# HV_Power_Stage.net
KiCad netlist of a schematic drawn in Altium Designer
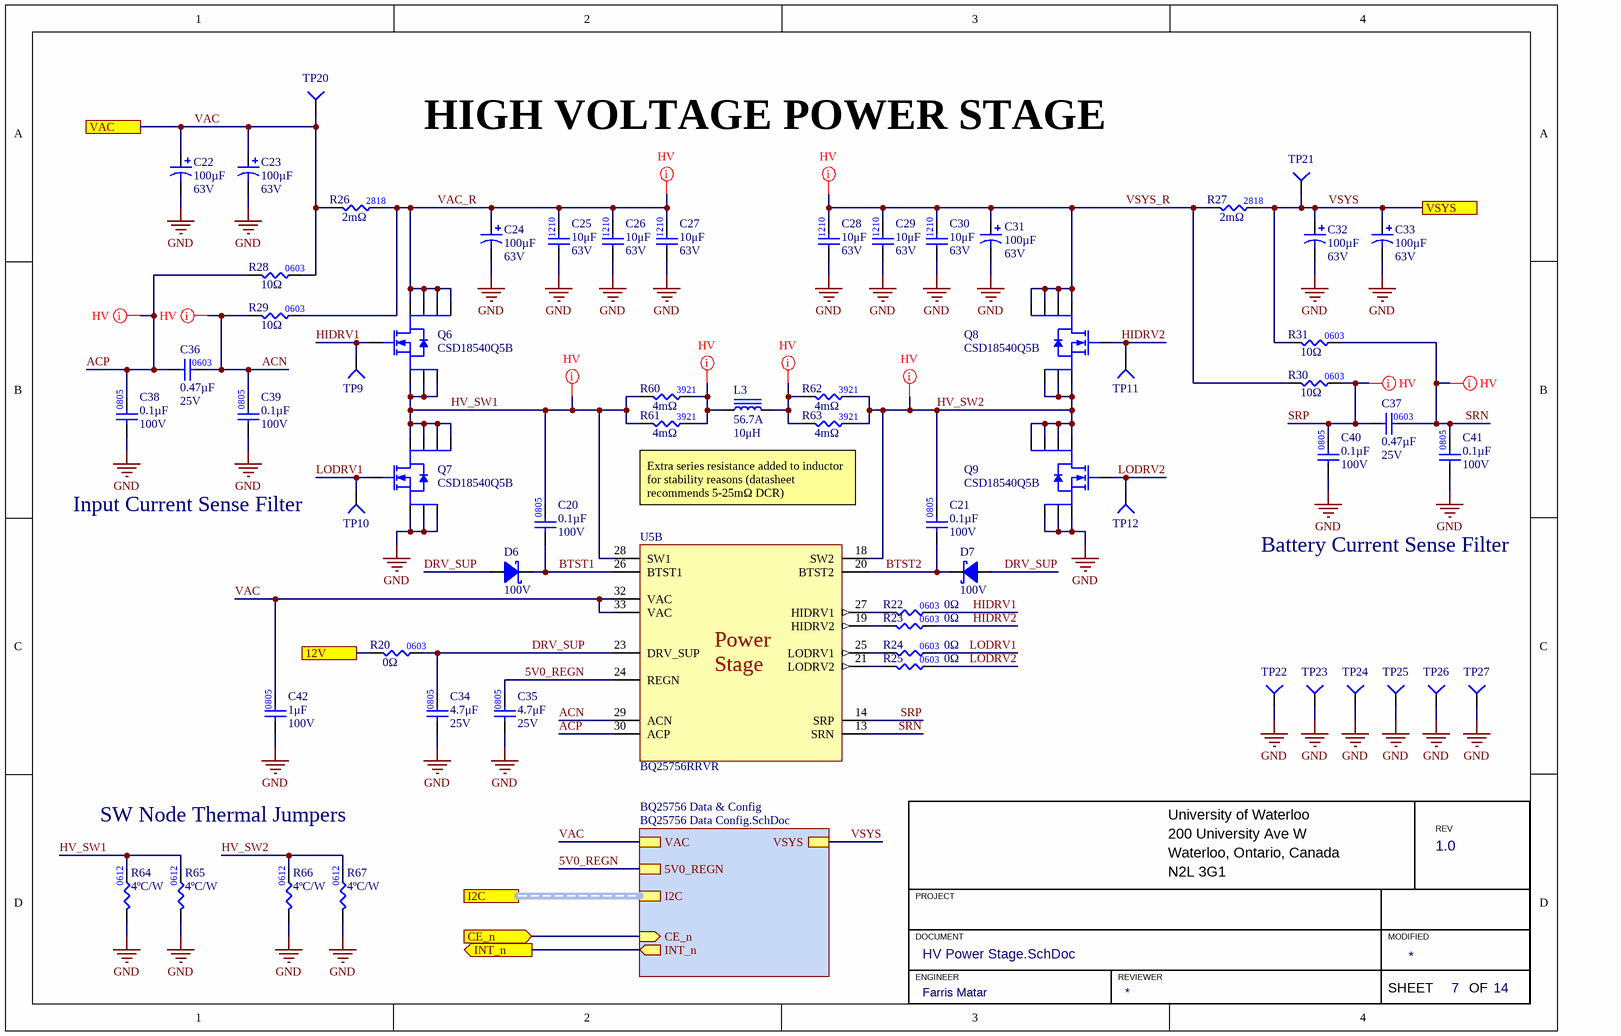
[diagram p0: HV Power Stage.SchDoc]

(export (version "E")
  (design (tool "Eeschema 10.0.6"))
  (components
    (comp (ref "C20")
      (value "0.1µF")
      (footprint "CAP0805")
      (description "CAP CER 0.1UF 100V X7R 0805")
      (fields (field (name "VOLTAGE RATING") "100V") (field (name "Comment") "CAP_0.1uF_100V_0805"))
      (libsource (lib "Personal_Schematic_Library_2022") (part "CAP_0.1uF_100V_0805"))
    )
    (comp (ref "C21")
      (value "0.1µF")
      (footprint "CAP0805")
      (description "CAP CER 0.1UF 100V X7R 0805")
      (fields (field (name "VOLTAGE RATING") "100V") (field (name "Comment") "CAP_0.1uF_100V_0805"))
      (libsource (lib "Personal_Schematic_Library_2022") (part "CAP_0.1uF_100V_0805"))
    )
    (comp (ref "C22")
      (value "100µF")
      (footprint "RADIAL_KEMET_A781")
      (description "CAP ALUMHYB 100UF 20% 63V SMD")
      (fields (field (name "VOLTAGE RATING") "63V") (field (name "Comment") "CAP_100uF_63V_ALUMHYB"))
      (libsource (lib "Personal_Schematic_Library_2022") (part "CAP_100uF_63V_ALUMHYB"))
    )
    (comp (ref "C23")
      (value "100µF")
      (footprint "RADIAL_KEMET_A781")
      (description "CAP ALUMHYB 100UF 20% 63V SMD")
      (fields (field (name "VOLTAGE RATING") "63V") (field (name "Comment") "CAP_100uF_63V_ALUMHYB"))
      (libsource (lib "Personal_Schematic_Library_2022") (part "CAP_100uF_63V_ALUMHYB"))
    )
    (comp (ref "C24")
      (value "100µF")
      (footprint "RADIAL_KEMET_A781")
      (description "CAP ALUMHYB 100UF 20% 63V SMD")
      (fields (field (name "VOLTAGE RATING") "63V") (field (name "Comment") "CAP_100uF_63V_ALUMHYB"))
      (libsource (lib "Personal_Schematic_Library_2022") (part "CAP_100uF_63V_ALUMHYB"))
    )
    (comp (ref "C25")
      (value "10μF")
      (footprint "CAP1210")
      (description "CAP CER 10UF 63V X7R 1210")
      (fields (field (name "VOLTAGE RATING") "63V") (field (name "Comment") "CAP_10uF_63V_1210"))
      (libsource (lib "Personal_Schematic_Library_2022") (part "CAP_10uF_63V_1210"))
    )
    (comp (ref "C26")
      (value "10μF")
      (footprint "CAP1210")
      (description "CAP CER 10UF 63V X7R 1210")
      (fields (field (name "VOLTAGE RATING") "63V") (field (name "Comment") "CAP_10uF_63V_1210"))
      (libsource (lib "Personal_Schematic_Library_2022") (part "CAP_10uF_63V_1210"))
    )
    (comp (ref "C27")
      (value "10μF")
      (footprint "CAP1210")
      (description "CAP CER 10UF 63V X7R 1210")
      (fields (field (name "VOLTAGE RATING") "63V") (field (name "Comment") "CAP_10uF_63V_1210"))
      (libsource (lib "Personal_Schematic_Library_2022") (part "CAP_10uF_63V_1210"))
    )
    (comp (ref "C28")
      (value "10μF")
      (footprint "CAP1210")
      (description "CAP CER 10UF 63V X7R 1210")
      (fields (field (name "VOLTAGE RATING") "63V") (field (name "Comment") "CAP_10uF_63V_1210"))
      (libsource (lib "Personal_Schematic_Library_2022") (part "CAP_10uF_63V_1210"))
    )
    (comp (ref "C29")
      (value "10μF")
      (footprint "CAP1210")
      (description "CAP CER 10UF 63V X7R 1210")
      (fields (field (name "VOLTAGE RATING") "63V") (field (name "Comment") "CAP_10uF_63V_1210"))
      (libsource (lib "Personal_Schematic_Library_2022") (part "CAP_10uF_63V_1210"))
    )
    (comp (ref "C30")
      (value "10μF")
      (footprint "CAP1210")
      (description "CAP CER 10UF 63V X7R 1210")
      (fields (field (name "VOLTAGE RATING") "63V") (field (name "Comment") "CAP_10uF_63V_1210"))
      (libsource (lib "Personal_Schematic_Library_2022") (part "CAP_10uF_63V_1210"))
    )
    (comp (ref "C31")
      (value "100µF")
      (footprint "RADIAL_KEMET_A781")
      (description "CAP ALUMHYB 100UF 20% 63V SMD")
      (fields (field (name "VOLTAGE RATING") "63V") (field (name "Comment") "CAP_100uF_63V_ALUMHYB"))
      (libsource (lib "Personal_Schematic_Library_2022") (part "CAP_100uF_63V_ALUMHYB"))
    )
    (comp (ref "C32")
      (value "100µF")
      (footprint "RADIAL_KEMET_A781")
      (description "CAP ALUMHYB 100UF 20% 63V SMD")
      (fields (field (name "VOLTAGE RATING") "63V") (field (name "Comment") "CAP_100uF_63V_ALUMHYB"))
      (libsource (lib "Personal_Schematic_Library_2022") (part "CAP_100uF_63V_ALUMHYB"))
    )
    (comp (ref "C33")
      (value "100µF")
      (footprint "RADIAL_KEMET_A781")
      (description "CAP ALUMHYB 100UF 20% 63V SMD")
      (fields (field (name "VOLTAGE RATING") "63V") (field (name "Comment") "CAP_100uF_63V_ALUMHYB"))
      (libsource (lib "Personal_Schematic_Library_2022") (part "CAP_100uF_63V_ALUMHYB"))
    )
    (comp (ref "C34")
      (value "4.7μF")
      (footprint "CAP0805")
      (description "CAP CER 4.7UF 25V X7R 0805")
      (fields (field (name "VOLTAGE RATING") "25V") (field (name "Comment") "CAP_4.7uF_25V_0805"))
      (libsource (lib "Personal_Schematic_Library_2022") (part "CAP_4.7uF_25V_0805"))
    )
    (comp (ref "C35")
      (value "4.7μF")
      (footprint "CAP0805")
      (description "CAP CER 4.7UF 25V X7R 0805")
      (fields (field (name "VOLTAGE RATING") "25V") (field (name "Comment") "CAP_4.7uF_25V_0805"))
      (libsource (lib "Personal_Schematic_Library_2022") (part "CAP_4.7uF_25V_0805"))
    )
    (comp (ref "C36")
      (value "0.47µF")
      (footprint "CAP0603")
      (description "CAP CER 0.47UF 25V X7R 0603")
      (fields (field (name "VOLTAGE RATING") "25V") (field (name "Comment") "CAP_0.47uF_25V_0603"))
      (libsource (lib "Personal_Schematic_Library_2022") (part "CAP_0.47uF_25V_0603"))
    )
    (comp (ref "C37")
      (value "0.47µF")
      (footprint "CAP0603")
      (description "CAP CER 0.47UF 25V X7R 0603")
      (fields (field (name "VOLTAGE RATING") "25V") (field (name "Comment") "CAP_0.47uF_25V_0603"))
      (libsource (lib "Personal_Schematic_Library_2022") (part "CAP_0.47uF_25V_0603"))
    )
    (comp (ref "C38")
      (value "0.1µF")
      (footprint "CAP0805")
      (description "CAP CER 0.1UF 100V X7R 0805")
      (fields (field (name "VOLTAGE RATING") "100V") (field (name "Comment") "CAP_0.1uF_100V_0805"))
      (libsource (lib "Personal_Schematic_Library_2022") (part "CAP_0.1uF_100V_0805"))
    )
    (comp (ref "C39")
      (value "0.1µF")
      (footprint "CAP0805")
      (description "CAP CER 0.1UF 100V X7R 0805")
      (fields (field (name "VOLTAGE RATING") "100V") (field (name "Comment") "CAP_0.1uF_100V_0805"))
      (libsource (lib "Personal_Schematic_Library_2022") (part "CAP_0.1uF_100V_0805"))
    )
    (comp (ref "C40")
      (value "0.1µF")
      (footprint "CAP0805")
      (description "CAP CER 0.1UF 100V X7R 0805")
      (fields (field (name "VOLTAGE RATING") "100V") (field (name "Comment") "CAP_0.1uF_100V_0805"))
      (libsource (lib "Personal_Schematic_Library_2022") (part "CAP_0.1uF_100V_0805"))
    )
    (comp (ref "C41")
      (value "0.1µF")
      (footprint "CAP0805")
      (description "CAP CER 0.1UF 100V X7R 0805")
      (fields (field (name "VOLTAGE RATING") "100V") (field (name "Comment") "CAP_0.1uF_100V_0805"))
      (libsource (lib "Personal_Schematic_Library_2022") (part "CAP_0.1uF_100V_0805"))
    )
    (comp (ref "C42")
      (value "1μF")
      (footprint "CAP0805")
      (description "CAP CER 1UF 100V X7R 0805")
      (fields (field (name "VOLTAGE RATING") "100V") (field (name "Comment") "CAP_1uF_100V_0805"))
      (libsource (lib "Personal_Schematic_Library_2022") (part "CAP_1uF_100V_0805"))
    )
    (comp (ref "D6")
      (value "DIO_SCHOTTKY_100V_2A")
      (footprint "SOD-123_FLAT")
      (description "DIODE SCHOTTKY 100V 2A SOD123F")
      (fields (field (name "VR (MAX)") "100V"))
      (libsource (lib "Personal_Schematic_Library_2022") (part "DIO_SCHOTTKY_100V_2A"))
    )
    (comp (ref "D7")
      (value "DIO_SCHOTTKY_100V_2A")
      (footprint "SOD-123_FLAT")
      (description "DIODE SCHOTTKY 100V 2A SOD123F")
      (fields (field (name "VR (MAX)") "100V"))
      (libsource (lib "Personal_Schematic_Library_2022") (part "DIO_SCHOTTKY_100V_2A"))
    )
    (comp (ref "L3")
      (value "IND_10uH_56.7A")
      (footprint "IND_WURTH_HCFT_TH")
      (description "FIXED IND 10UH 56.7A 1.2 MOHM TH")
      (fields (field (name "CURRENT RATING") "56.7A") (field (name "INDUCTANCE") "10μH"))
      (libsource (lib "Personal_Schematic_Library_2022") (part "IND_10uH_56.7A"))
    )
    (comp (ref "Q6")
      (value "NMOS_60V_100A_TI")
      (footprint "DFN5060")
      (description "MOSFET N-CH 60V 100A 8VSON")
      (fields (field (name "MANUFACTURER PART NUMBER 1") "CSD18540Q5B"))
      (libsource (lib "Personal_Schematic_Library_2022") (part "NMOS_60V_100A_TI"))
    )
    (comp (ref "Q7")
      (value "NMOS_60V_100A_TI")
      (footprint "DFN5060")
      (description "MOSFET N-CH 60V 100A 8VSON")
      (fields (field (name "MANUFACTURER PART NUMBER 1") "CSD18540Q5B"))
      (libsource (lib "Personal_Schematic_Library_2022") (part "NMOS_60V_100A_TI"))
    )
    (comp (ref "Q8")
      (value "NMOS_60V_100A_TI")
      (footprint "DFN5060")
      (description "MOSFET N-CH 60V 100A 8VSON")
      (fields (field (name "MANUFACTURER PART NUMBER 1") "CSD18540Q5B"))
      (libsource (lib "Personal_Schematic_Library_2022") (part "NMOS_60V_100A_TI"))
    )
    (comp (ref "Q9")
      (value "NMOS_60V_100A_TI")
      (footprint "DFN5060")
      (description "MOSFET N-CH 60V 100A 8VSON")
      (fields (field (name "MANUFACTURER PART NUMBER 1") "CSD18540Q5B"))
      (libsource (lib "Personal_Schematic_Library_2022") (part "NMOS_60V_100A_TI"))
    )
    (comp (ref "R20")
      (value "0Ω")
      (footprint "RES0603")
      (description "RES 0 OHM JUMPER 1/10W 0603")
      (fields (field (name "Comment") "RES_0Ω_0603"))
      (libsource (lib "Personal_Schematic_Library_2022") (part "RES_0Ω_0603"))
    )
    (comp (ref "R22")
      (value "0Ω")
      (footprint "RES0603")
      (description "RES 0 OHM JUMPER 1/10W 0603")
      (fields (field (name "Comment") "RES_0Ω_0603"))
      (libsource (lib "Personal_Schematic_Library_2022") (part "RES_0Ω_0603"))
    )
    (comp (ref "R23")
      (value "0Ω")
      (footprint "RES0603")
      (description "RES 0 OHM JUMPER 1/10W 0603")
      (fields (field (name "Comment") "RES_0Ω_0603"))
      (libsource (lib "Personal_Schematic_Library_2022") (part "RES_0Ω_0603"))
    )
    (comp (ref "R24")
      (value "0Ω")
      (footprint "RES0603")
      (description "RES 0 OHM JUMPER 1/10W 0603")
      (fields (field (name "Comment") "RES_0Ω_0603"))
      (libsource (lib "Personal_Schematic_Library_2022") (part "RES_0Ω_0603"))
    )
    (comp (ref "R25")
      (value "0Ω")
      (footprint "RES0603")
      (description "RES 0 OHM JUMPER 1/10W 0603")
      (fields (field (name "Comment") "RES_0Ω_0603"))
      (libsource (lib "Personal_Schematic_Library_2022") (part "RES_0Ω_0603"))
    )
    (comp (ref "R26")
      (value "2mΩ")
      (footprint "RES2812_VISHAY")
      (description "RES 0.002 OHM 1% 10W 2818")
      (fields (field (name "Comment") "RES_2mΩ_2818_1%"))
      (libsource (lib "Personal_Schematic_Library_2022") (part "RES_2mΩ_2818_1%"))
    )
    (comp (ref "R27")
      (value "2mΩ")
      (footprint "RES2812_VISHAY")
      (description "RES 0.002 OHM 1% 10W 2818")
      (fields (field (name "Comment") "RES_2mΩ_2818_1%"))
      (libsource (lib "Personal_Schematic_Library_2022") (part "RES_2mΩ_2818_1%"))
    )
    (comp (ref "R28")
      (value "10Ω")
      (footprint "RES0603")
      (description "RES 10 OHM 1% 1/10W 0603")
      (fields (field (name "Comment") "RES_10Ω_0603_1%"))
      (libsource (lib "Personal_Schematic_Library_2022") (part "RES_10Ω_0603_1%"))
    )
    (comp (ref "R29")
      (value "10Ω")
      (footprint "RES0603")
      (description "RES 10 OHM 1% 1/10W 0603")
      (fields (field (name "Comment") "RES_10Ω_0603_1%"))
      (libsource (lib "Personal_Schematic_Library_2022") (part "RES_10Ω_0603_1%"))
    )
    (comp (ref "R30")
      (value "10Ω")
      (footprint "RES0603")
      (description "RES 10 OHM 1% 1/10W 0603")
      (fields (field (name "Comment") "RES_10Ω_0603_1%"))
      (libsource (lib "Personal_Schematic_Library_2022") (part "RES_10Ω_0603_1%"))
    )
    (comp (ref "R31")
      (value "10Ω")
      (footprint "RES0603")
      (description "RES 10 OHM 1% 1/10W 0603")
      (fields (field (name "Comment") "RES_10Ω_0603_1%"))
      (libsource (lib "Personal_Schematic_Library_2022") (part "RES_10Ω_0603_1%"))
    )
    (comp (ref "R60")
      (value "4mΩ")
      (footprint "RES3921")
      (description "RES 0.004 OHM 1% 5W 3921")
      (fields (field (name "Comment") "RES_4mΩ_3921_1%"))
      (libsource (lib "Personal_Schematic_Library_2022") (part "RES_4mΩ_3921_1%"))
    )
    (comp (ref "R61")
      (value "4mΩ")
      (footprint "RES3921")
      (description "RES 0.004 OHM 1% 5W 3921")
      (fields (field (name "Comment") "RES_4mΩ_3921_1%"))
      (libsource (lib "Personal_Schematic_Library_2022") (part "RES_4mΩ_3921_1%"))
    )
    (comp (ref "R62")
      (value "4mΩ")
      (footprint "RES3921")
      (description "RES 0.004 OHM 1% 5W 3921")
      (fields (field (name "Comment") "RES_4mΩ_3921_1%"))
      (libsource (lib "Personal_Schematic_Library_2022") (part "RES_4mΩ_3921_1%"))
    )
    (comp (ref "R63")
      (value "4mΩ")
      (footprint "RES3921")
      (description "RES 0.004 OHM 1% 5W 3921")
      (fields (field (name "Comment") "RES_4mΩ_3921_1%"))
      (libsource (lib "Personal_Schematic_Library_2022") (part "RES_4mΩ_3921_1%"))
    )
    (comp (ref "R64")
      (value "4ºC/W")
      (footprint "RES0612")
      (description "THERMAL JUMPER 0612 30 MIL LEAD-")
      (fields (field (name "Comment") "THERM_JMP_4C_0612"))
      (libsource (lib "Personal_Schematic_Library_2022") (part "THERM_JMP_4C_0612"))
    )
    (comp (ref "R65")
      (value "4ºC/W")
      (footprint "RES0612")
      (description "THERMAL JUMPER 0612 30 MIL LEAD-")
      (fields (field (name "Comment") "THERM_JMP_4C_0612"))
      (libsource (lib "Personal_Schematic_Library_2022") (part "THERM_JMP_4C_0612"))
    )
    (comp (ref "R66")
      (value "4ºC/W")
      (footprint "RES0612")
      (description "THERMAL JUMPER 0612 30 MIL LEAD-")
      (fields (field (name "Comment") "THERM_JMP_4C_0612"))
      (libsource (lib "Personal_Schematic_Library_2022") (part "THERM_JMP_4C_0612"))
    )
    (comp (ref "R67")
      (value "4ºC/W")
      (footprint "RES0612")
      (description "THERMAL JUMPER 0612 30 MIL LEAD-")
      (fields (field (name "Comment") "THERM_JMP_4C_0612"))
      (libsource (lib "Personal_Schematic_Library_2022") (part "THERM_JMP_4C_0612"))
    )
    (comp (ref "TP9")
      (value "TESTPOINT_1MM_CIRCLE")
      (footprint "TESTPOINT_CIRCLE_1MM")
      (description "TESTPOINT 1MM CIRCLE")
      (libsource (lib "Personal_Schematic_Library_2022") (part "TESTPOINT_1MM_CIRCLE"))
    )
    (comp (ref "TP10")
      (value "TESTPOINT_1MM_CIRCLE")
      (footprint "TESTPOINT_CIRCLE_1MM")
      (description "TESTPOINT 1MM CIRCLE")
      (libsource (lib "Personal_Schematic_Library_2022") (part "TESTPOINT_1MM_CIRCLE"))
    )
    (comp (ref "TP11")
      (value "TESTPOINT_1MM_CIRCLE")
      (footprint "TESTPOINT_CIRCLE_1MM")
      (description "TESTPOINT 1MM CIRCLE")
      (libsource (lib "Personal_Schematic_Library_2022") (part "TESTPOINT_1MM_CIRCLE"))
    )
    (comp (ref "TP12")
      (value "TESTPOINT_1MM_CIRCLE")
      (footprint "TESTPOINT_CIRCLE_1MM")
      (description "TESTPOINT 1MM CIRCLE")
      (libsource (lib "Personal_Schematic_Library_2022") (part "TESTPOINT_1MM_CIRCLE"))
    )
    (comp (ref "TP20")
      (value "TESTPOINT_KEYSTONE_LOOP")
      (footprint "KEYSTONE_5019")
      (description "PC TEST POINT MINIATURE")
      (libsource (lib "Personal_Schematic_Library_2022") (part "TESTPOINT_KEYSTONE_LOOP"))
    )
    (comp (ref "TP21")
      (value "TESTPOINT_KEYSTONE_LOOP")
      (footprint "KEYSTONE_5019")
      (description "PC TEST POINT MINIATURE")
      (libsource (lib "Personal_Schematic_Library_2022") (part "TESTPOINT_KEYSTONE_LOOP"))
    )
    (comp (ref "TP22")
      (value "TESTPOINT_KEYSTONE_LOOP")
      (footprint "KEYSTONE_5019")
      (description "PC TEST POINT MINIATURE")
      (libsource (lib "Personal_Schematic_Library_2022") (part "TESTPOINT_KEYSTONE_LOOP"))
    )
    (comp (ref "TP23")
      (value "TESTPOINT_KEYSTONE_LOOP")
      (footprint "KEYSTONE_5019")
      (description "PC TEST POINT MINIATURE")
      (libsource (lib "Personal_Schematic_Library_2022") (part "TESTPOINT_KEYSTONE_LOOP"))
    )
    (comp (ref "TP24")
      (value "TESTPOINT_KEYSTONE_LOOP")
      (footprint "KEYSTONE_5019")
      (description "PC TEST POINT MINIATURE")
      (libsource (lib "Personal_Schematic_Library_2022") (part "TESTPOINT_KEYSTONE_LOOP"))
    )
    (comp (ref "TP25")
      (value "TESTPOINT_KEYSTONE_LOOP")
      (footprint "KEYSTONE_5019")
      (description "PC TEST POINT MINIATURE")
      (libsource (lib "Personal_Schematic_Library_2022") (part "TESTPOINT_KEYSTONE_LOOP"))
    )
    (comp (ref "TP26")
      (value "TESTPOINT_KEYSTONE_LOOP")
      (footprint "KEYSTONE_5019")
      (description "PC TEST POINT MINIATURE")
      (libsource (lib "Personal_Schematic_Library_2022") (part "TESTPOINT_KEYSTONE_LOOP"))
    )
    (comp (ref "TP27")
      (value "TESTPOINT_KEYSTONE_LOOP")
      (footprint "KEYSTONE_5019")
      (description "PC TEST POINT MINIATURE")
      (libsource (lib "Personal_Schematic_Library_2022") (part "TESTPOINT_KEYSTONE_LOOP"))
    )
    (comp (ref "U5")
      (value "BQ25756RRVR")
      (footprint "TI_36-VQFN")
      (description "IC BATT CHARGER BUCK-BOOST CTRLR")
      (libsource (lib "Personal_Schematic_Library_2022") (part "BQ25756RRVR"))
    )
  )
  (nets
    (net (code "2") (name "/5V0_REGN") (class "Default")
      (node (ref "C35") (pin "2") (pinfunction "2_2") (pintype "passive"))
      (node (ref "U5") (pin "24") (pinfunction "REGN_24") (pintype "power_in"))
    )
    (net (code "3") (name "/12V") (class "Default")
      (node (ref "R20") (pin "1") (pinfunction "1_1") (pintype "passive"))
    )
    (net (code "4") (name "/ACN") (class "Default")
      (node (ref "C36") (pin "2") (pinfunction "2_2") (pintype "passive"))
      (node (ref "C39") (pin "2") (pinfunction "2_2") (pintype "passive"))
      (node (ref "R29") (pin "1") (pinfunction "1_1") (pintype "passive"))
      (node (ref "U5") (pin "29") (pinfunction "ACN_29") (pintype "passive"))
    )
    (net (code "5") (name "/ACP") (class "Default")
      (node (ref "C36") (pin "1") (pinfunction "1_1") (pintype "passive"))
      (node (ref "C38") (pin "2") (pinfunction "2_2") (pintype "passive"))
      (node (ref "R28") (pin "1") (pinfunction "1_1") (pintype "passive"))
      (node (ref "U5") (pin "30") (pinfunction "ACP_30") (pintype "passive"))
    )
    (net (code "6") (name "/BTST1") (class "Default")
      (node (ref "C20") (pin "1") (pinfunction "1_1") (pintype "passive"))
      (node (ref "D6") (pin "2") (pinfunction "Cathode_2") (pintype "passive"))
      (node (ref "U5") (pin "26") (pinfunction "BTST1_26") (pintype "power_in"))
    )
    (net (code "7") (name "/BTST2") (class "Default")
      (node (ref "C21") (pin "1") (pinfunction "1_1") (pintype "passive"))
      (node (ref "D7") (pin "2") (pinfunction "Cathode_2") (pintype "passive"))
      (node (ref "U5") (pin "20") (pinfunction "BTST2_20") (pintype "power_in"))
    )
    (net (code "9") (name "/DRV_SUP") (class "Default")
      (node (ref "C34") (pin "2") (pinfunction "2_2") (pintype "passive"))
      (node (ref "D6") (pin "1") (pinfunction "Anode_1") (pintype "passive"))
      (node (ref "D7") (pin "1") (pinfunction "Anode_1") (pintype "passive"))
      (node (ref "R20") (pin "2") (pinfunction "2_2") (pintype "passive"))
      (node (ref "U5") (pin "23") (pinfunction "DRV_SUP_23") (pintype "power_in"))
    )
    (net (code "10") (name "/HIDRV1") (class "Default")
      (node (ref "Q6") (pin "4") (pinfunction "Gate_4") (pintype "passive"))
      (node (ref "R22") (pin "2") (pinfunction "2_2") (pintype "passive"))
      (node (ref "TP9") (pin "1") (pinfunction "=value_1") (pintype "passive"))
    )
    (net (code "11") (name "/HIDRV2") (class "Default")
      (node (ref "Q8") (pin "4") (pinfunction "Gate_4") (pintype "passive"))
      (node (ref "R23") (pin "2") (pinfunction "2_2") (pintype "passive"))
      (node (ref "TP11") (pin "1") (pinfunction "=value_1") (pintype "passive"))
    )
    (net (code "12") (name "/HV_SW1") (class "Default")
      (node (ref "C20") (pin "2") (pinfunction "2_2") (pintype "passive"))
      (node (ref "Q6") (pin "1") (pinfunction "Source_1") (pintype "passive"))
      (node (ref "Q6") (pin "2") (pinfunction "Source_2") (pintype "passive"))
      (node (ref "Q6") (pin "3") (pinfunction "Source_3") (pintype "passive"))
      (node (ref "Q7") (pin "5") (pinfunction "Drain_5") (pintype "passive"))
      (node (ref "Q7") (pin "6") (pinfunction "Drain_6") (pintype "passive"))
      (node (ref "Q7") (pin "7") (pinfunction "Drain_7") (pintype "passive"))
      (node (ref "Q7") (pin "8") (pinfunction "Drain_8") (pintype "passive"))
      (node (ref "R60") (pin "1") (pinfunction "1_1") (pintype "passive"))
      (node (ref "R61") (pin "1") (pinfunction "1_1") (pintype "passive"))
      (node (ref "R64") (pin "2") (pinfunction "2_2") (pintype "passive"))
      (node (ref "R65") (pin "2") (pinfunction "2_2") (pintype "passive"))
      (node (ref "U5") (pin "28") (pinfunction "SW1_28") (pintype "power_in"))
    )
    (net (code "13") (name "/HV_SW2") (class "Default")
      (node (ref "C21") (pin "2") (pinfunction "2_2") (pintype "passive"))
      (node (ref "Q8") (pin "1") (pinfunction "Source_1") (pintype "passive"))
      (node (ref "Q8") (pin "2") (pinfunction "Source_2") (pintype "passive"))
      (node (ref "Q8") (pin "3") (pinfunction "Source_3") (pintype "passive"))
      (node (ref "Q9") (pin "5") (pinfunction "Drain_5") (pintype "passive"))
      (node (ref "Q9") (pin "6") (pinfunction "Drain_6") (pintype "passive"))
      (node (ref "Q9") (pin "7") (pinfunction "Drain_7") (pintype "passive"))
      (node (ref "Q9") (pin "8") (pinfunction "Drain_8") (pintype "passive"))
      (node (ref "R62") (pin "2") (pinfunction "2_2") (pintype "passive"))
      (node (ref "R63") (pin "2") (pinfunction "2_2") (pintype "passive"))
      (node (ref "R66") (pin "2") (pinfunction "2_2") (pintype "passive"))
      (node (ref "R67") (pin "2") (pinfunction "2_2") (pintype "passive"))
      (node (ref "U5") (pin "18") (pinfunction "SW2_18") (pintype "power_in"))
    )
    (net (code "16") (name "/LODRV1") (class "Default")
      (node (ref "Q7") (pin "4") (pinfunction "Gate_4") (pintype "passive"))
      (node (ref "R24") (pin "2") (pinfunction "2_2") (pintype "passive"))
      (node (ref "TP10") (pin "1") (pinfunction "=value_1") (pintype "passive"))
    )
    (net (code "17") (name "/LODRV2") (class "Default")
      (node (ref "Q9") (pin "4") (pinfunction "Gate_4") (pintype "passive"))
      (node (ref "R25") (pin "2") (pinfunction "2_2") (pintype "passive"))
      (node (ref "TP12") (pin "1") (pinfunction "=value_1") (pintype "passive"))
    )
    (net (code "18") (name "/SRN") (class "Default")
      (node (ref "C37") (pin "2") (pinfunction "2_2") (pintype "passive"))
      (node (ref "C41") (pin "2") (pinfunction "2_2") (pintype "passive"))
      (node (ref "R31") (pin "2") (pinfunction "2_2") (pintype "passive"))
      (node (ref "U5") (pin "13") (pinfunction "SRN_13") (pintype "passive"))
    )
    (net (code "19") (name "/SRP") (class "Default")
      (node (ref "C37") (pin "1") (pinfunction "1_1") (pintype "passive"))
      (node (ref "C40") (pin "2") (pinfunction "2_2") (pintype "passive"))
      (node (ref "R30") (pin "2") (pinfunction "2_2") (pintype "passive"))
      (node (ref "U5") (pin "14") (pinfunction "SRP_14") (pintype "passive"))
    )
    (net (code "20") (name "/VAC") (class "Default")
      (node (ref "C22") (pin "1") (pinfunction "1_1") (pintype "passive"))
      (node (ref "C23") (pin "1") (pinfunction "1_1") (pintype "passive"))
      (node (ref "C42") (pin "2") (pinfunction "2_2") (pintype "passive"))
      (node (ref "R26") (pin "1") (pinfunction "1_1") (pintype "passive"))
      (node (ref "R28") (pin "2") (pinfunction "2_2") (pintype "passive"))
      (node (ref "TP20") (pin "1") (pinfunction "=value_1") (pintype "passive"))
      (node (ref "U5") (pin "32") (pinfunction "VAC_32") (pintype "power_in"))
      (node (ref "U5") (pin "33") (pinfunction "VAC_33") (pintype "power_in"))
    )
    (net (code "21") (name "/VAC_R") (class "Default")
      (node (ref "C24") (pin "1") (pinfunction "1_1") (pintype "passive"))
      (node (ref "C25") (pin "2") (pinfunction "2_2") (pintype "passive"))
      (node (ref "C26") (pin "2") (pinfunction "2_2") (pintype "passive"))
      (node (ref "C27") (pin "2") (pinfunction "2_2") (pintype "passive"))
      (node (ref "Q6") (pin "5") (pinfunction "Drain_5") (pintype "passive"))
      (node (ref "Q6") (pin "6") (pinfunction "Drain_6") (pintype "passive"))
      (node (ref "Q6") (pin "7") (pinfunction "Drain_7") (pintype "passive"))
      (node (ref "Q6") (pin "8") (pinfunction "Drain_8") (pintype "passive"))
      (node (ref "R26") (pin "2") (pinfunction "2_2") (pintype "passive"))
      (node (ref "R29") (pin "2") (pinfunction "2_2") (pintype "passive"))
    )
    (net (code "22") (name "/VSYS") (class "Default")
      (node (ref "C32") (pin "1") (pinfunction "1_1") (pintype "passive"))
      (node (ref "C33") (pin "1") (pinfunction "1_1") (pintype "passive"))
      (node (ref "R27") (pin "2") (pinfunction "2_2") (pintype "passive"))
      (node (ref "R31") (pin "1") (pinfunction "1_1") (pintype "passive"))
      (node (ref "TP21") (pin "1") (pinfunction "=value_1") (pintype "passive"))
    )
    (net (code "23") (name "/VSYS_R") (class "Default")
      (node (ref "C28") (pin "2") (pinfunction "2_2") (pintype "passive"))
      (node (ref "C29") (pin "2") (pinfunction "2_2") (pintype "passive"))
      (node (ref "C30") (pin "2") (pinfunction "2_2") (pintype "passive"))
      (node (ref "C31") (pin "1") (pinfunction "1_1") (pintype "passive"))
      (node (ref "Q8") (pin "5") (pinfunction "Drain_5") (pintype "passive"))
      (node (ref "Q8") (pin "6") (pinfunction "Drain_6") (pintype "passive"))
      (node (ref "Q8") (pin "7") (pinfunction "Drain_7") (pintype "passive"))
      (node (ref "Q8") (pin "8") (pinfunction "Drain_8") (pintype "passive"))
      (node (ref "R27") (pin "1") (pinfunction "1_1") (pintype "passive"))
      (node (ref "R30") (pin "1") (pinfunction "1_1") (pintype "passive"))
    )
    (net (code "24") (name "GND") (class "Default")
      (node (ref "C22") (pin "2") (pinfunction "2_2") (pintype "passive"))
      (node (ref "C23") (pin "2") (pinfunction "2_2") (pintype "passive"))
      (node (ref "C24") (pin "2") (pinfunction "2_2") (pintype "passive"))
      (node (ref "C25") (pin "1") (pinfunction "1_1") (pintype "passive"))
      (node (ref "C26") (pin "1") (pinfunction "1_1") (pintype "passive"))
      (node (ref "C27") (pin "1") (pinfunction "1_1") (pintype "passive"))
      (node (ref "C28") (pin "1") (pinfunction "1_1") (pintype "passive"))
      (node (ref "C29") (pin "1") (pinfunction "1_1") (pintype "passive"))
      (node (ref "C30") (pin "1") (pinfunction "1_1") (pintype "passive"))
      (node (ref "C31") (pin "2") (pinfunction "2_2") (pintype "passive"))
      (node (ref "C32") (pin "2") (pinfunction "2_2") (pintype "passive"))
      (node (ref "C33") (pin "2") (pinfunction "2_2") (pintype "passive"))
      (node (ref "C34") (pin "1") (pinfunction "1_1") (pintype "passive"))
      (node (ref "C35") (pin "1") (pinfunction "1_1") (pintype "passive"))
      (node (ref "C38") (pin "1") (pinfunction "1_1") (pintype "passive"))
      (node (ref "C39") (pin "1") (pinfunction "1_1") (pintype "passive"))
      (node (ref "C40") (pin "1") (pinfunction "1_1") (pintype "passive"))
      (node (ref "C41") (pin "1") (pinfunction "1_1") (pintype "passive"))
      (node (ref "C42") (pin "1") (pinfunction "1_1") (pintype "passive"))
      (node (ref "Q7") (pin "1") (pinfunction "Source_1") (pintype "passive"))
      (node (ref "Q7") (pin "2") (pinfunction "Source_2") (pintype "passive"))
      (node (ref "Q7") (pin "3") (pinfunction "Source_3") (pintype "passive"))
      (node (ref "Q9") (pin "1") (pinfunction "Source_1") (pintype "passive"))
      (node (ref "Q9") (pin "2") (pinfunction "Source_2") (pintype "passive"))
      (node (ref "Q9") (pin "3") (pinfunction "Source_3") (pintype "passive"))
      (node (ref "R64") (pin "1") (pinfunction "1_1") (pintype "passive"))
      (node (ref "R65") (pin "1") (pinfunction "1_1") (pintype "passive"))
      (node (ref "R66") (pin "1") (pinfunction "1_1") (pintype "passive"))
      (node (ref "R67") (pin "1") (pinfunction "1_1") (pintype "passive"))
      (node (ref "TP22") (pin "1") (pinfunction "=value_1") (pintype "passive"))
      (node (ref "TP23") (pin "1") (pinfunction "=value_1") (pintype "passive"))
      (node (ref "TP24") (pin "1") (pinfunction "=value_1") (pintype "passive"))
      (node (ref "TP25") (pin "1") (pinfunction "=value_1") (pintype "passive"))
      (node (ref "TP26") (pin "1") (pinfunction "=value_1") (pintype "passive"))
      (node (ref "TP27") (pin "1") (pinfunction "=value_1") (pintype "passive"))
    )
    (net (code "25") (name "Net-(L3-Pad1)") (class "Default")
      (node (ref "L3") (pin "1") (pinfunction "1_1") (pintype "passive"))
      (node (ref "R60") (pin "2") (pinfunction "2_2") (pintype "passive"))
      (node (ref "R61") (pin "2") (pinfunction "2_2") (pintype "passive"))
    )
    (net (code "26") (name "Net-(L3-Pad2)") (class "Default")
      (node (ref "L3") (pin "2") (pinfunction "2_2") (pintype "passive"))
      (node (ref "R62") (pin "1") (pinfunction "1_1") (pintype "passive"))
      (node (ref "R63") (pin "1") (pinfunction "1_1") (pintype "passive"))
    )
    (net (code "27") (name "Net-(U5B-HIDRV1)") (class "Default")
      (node (ref "R22") (pin "1") (pinfunction "1_1") (pintype "passive"))
      (node (ref "U5") (pin "27") (pinfunction "HIDRV1_27") (pintype "output"))
    )
    (net (code "28") (name "Net-(U5B-HIDRV2)") (class "Default")
      (node (ref "R23") (pin "1") (pinfunction "1_1") (pintype "passive"))
      (node (ref "U5") (pin "19") (pinfunction "HIDRV2_19") (pintype "output"))
    )
    (net (code "29") (name "Net-(U5B-LODRV1)") (class "Default")
      (node (ref "R24") (pin "1") (pinfunction "1_1") (pintype "passive"))
      (node (ref "U5") (pin "25") (pinfunction "LODRV1_25") (pintype "output"))
    )
    (net (code "30") (name "Net-(U5B-LODRV2)") (class "Default")
      (node (ref "R25") (pin "1") (pinfunction "1_1") (pintype "passive"))
      (node (ref "U5") (pin "21") (pinfunction "LODRV2_21") (pintype "output"))
    )
  )
)
